# Adafruit_LSM9DS0_PCB.net
KiCad netlist of a schematic drawn in EAGLE
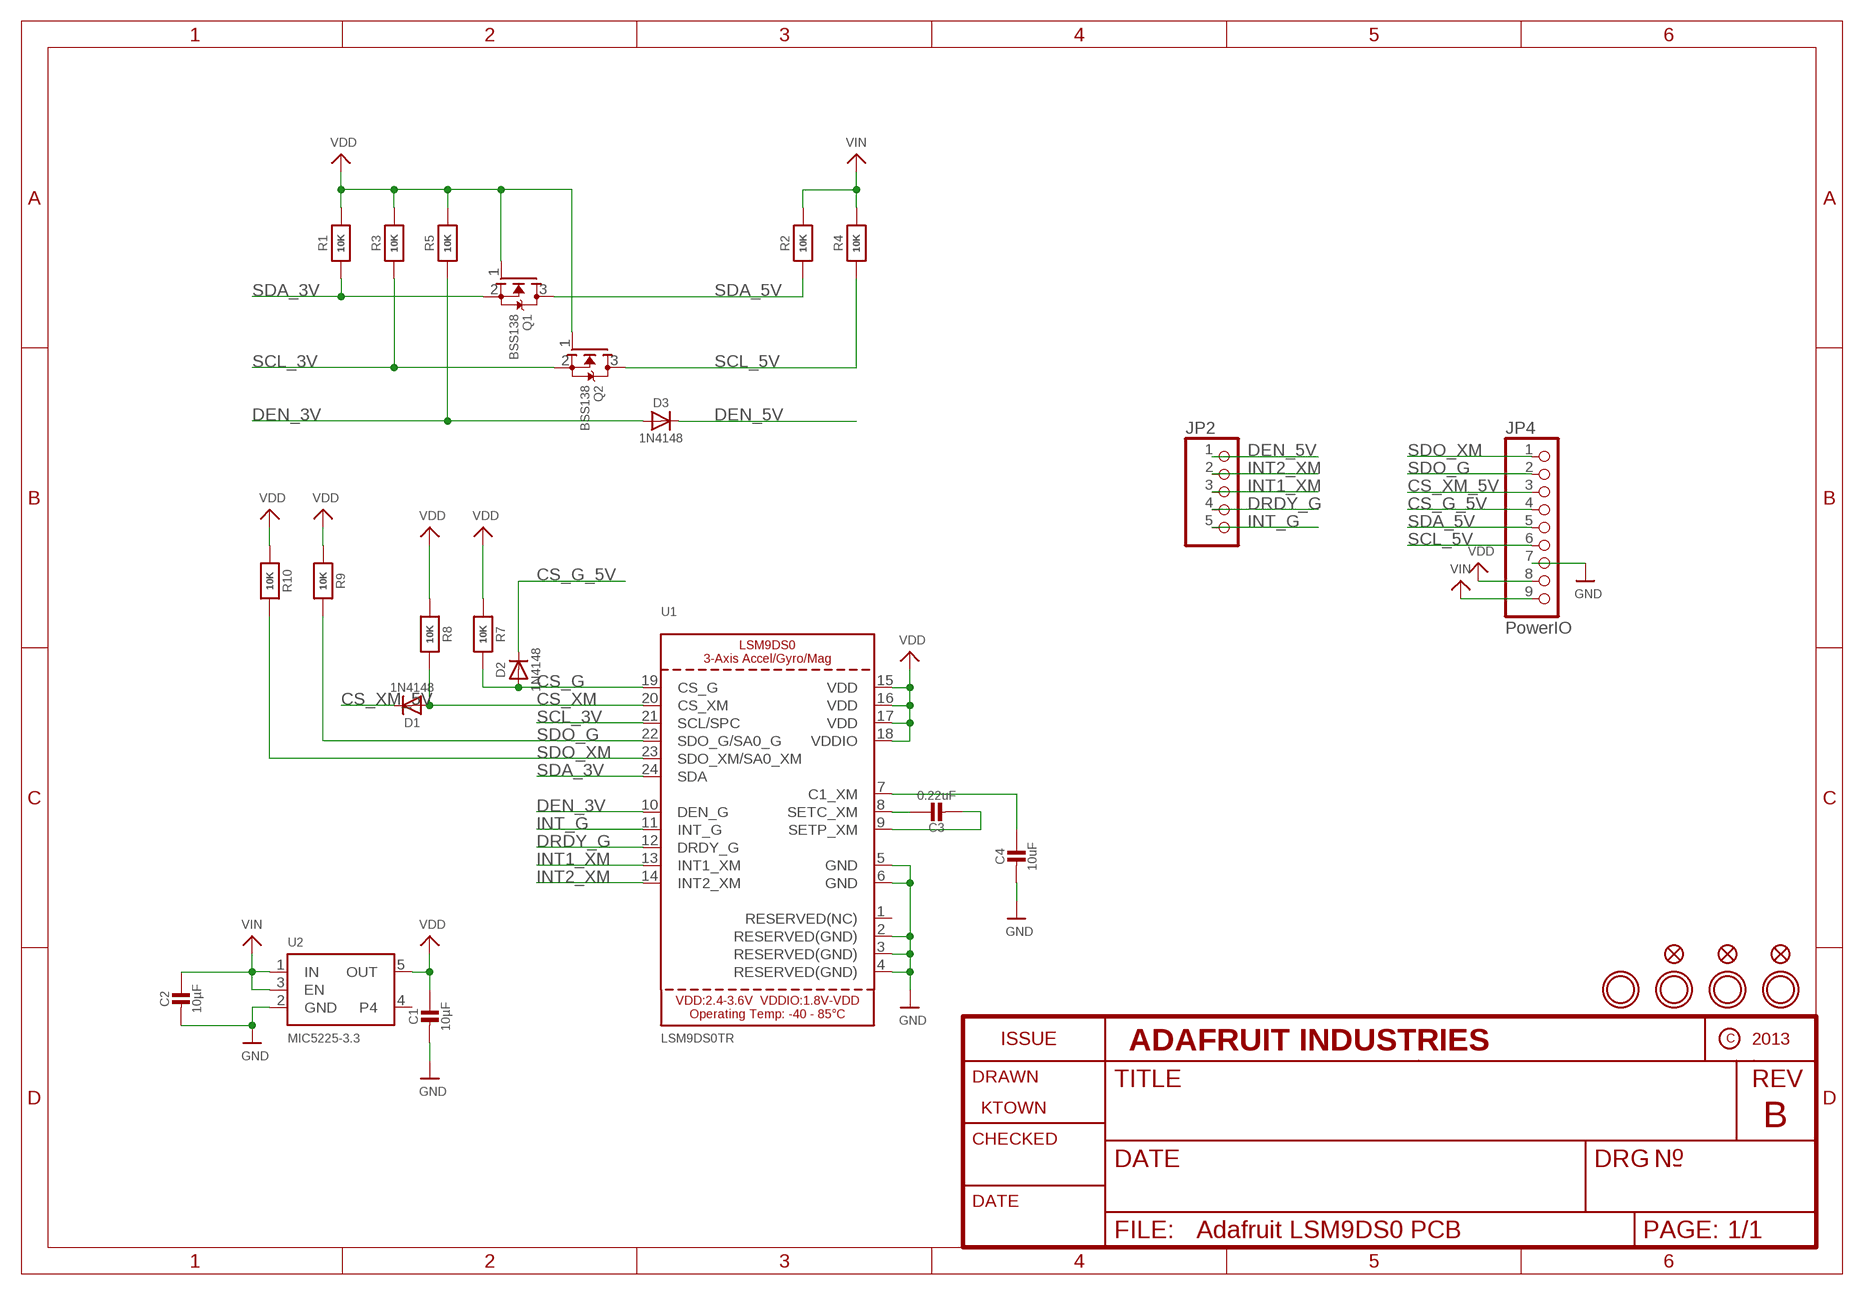
[diagram p0: schematic, sheet 1]

(export (version "E")
  (design (tool "Eeschema 10.0.6"))
  (components
    (comp (ref "C1")
      (value "10µF")
      (footprint "eagle-import:0805-NO")
      (libsource (lib "eagle-import") (part "CAP_CERAMIC0805-NOOUTLINE"))
    )
    (comp (ref "C2")
      (value "10µF")
      (footprint "eagle-import:0805-NO")
      (libsource (lib "eagle-import") (part "CAP_CERAMIC0805-NOOUTLINE"))
    )
    (comp (ref "C3")
      (value "0.22uF")
      (footprint "eagle-import:0805-NO")
      (libsource (lib "eagle-import") (part "CAP_CERAMIC0805-NOOUTLINE"))
    )
    (comp (ref "C4")
      (value "10uF")
      (footprint "eagle-import:0805-NO")
      (libsource (lib "eagle-import") (part "CAP_CERAMIC0805-NOOUTLINE"))
    )
    (comp (ref "D1")
      (value "1N4148")
      (footprint "eagle-import:SOD-323")
      (libsource (lib "eagle-import") (part "DIODESOD-323"))
    )
    (comp (ref "D2")
      (value "1N4148")
      (footprint "eagle-import:SOD-323")
      (libsource (lib "eagle-import") (part "DIODESOD-323"))
    )
    (comp (ref "D3")
      (value "1N4148")
      (footprint "eagle-import:SOD-323")
      (libsource (lib "eagle-import") (part "DIODESOD-323"))
    )
    (comp (ref "FID1")
      (value "FIDUCIAL\"\"")
      (footprint "eagle-import:FIDUCIAL_1MM")
      (libsource (lib "eagle-import") (part "FIDUCIAL{dblquote}{dblquote}"))
    )
    (comp (ref "FID2")
      (value "FIDUCIAL\"\"")
      (footprint "eagle-import:FIDUCIAL_1MM")
      (libsource (lib "eagle-import") (part "FIDUCIAL{dblquote}{dblquote}"))
    )
    (comp (ref "FID3")
      (value "FIDUCIAL\"\"")
      (footprint "eagle-import:FIDUCIAL_1MM")
      (fields (field (name "BOM") "EXCLUDE"))
      (libsource (lib "eagle-import") (part "FIDUCIAL{dblquote}{dblquote}"))
    )
    (comp (ref "JP2")
      (value "HEADER-1X570MIL")
      (footprint "eagle-import:1X05_ROUND_70")
      (libsource (lib "eagle-import") (part "HEADER-1X570MIL"))
    )
    (comp (ref "JP4")
      (value "PowerIO")
      (footprint "eagle-import:1X09_ROUND_70")
      (libsource (lib "eagle-import") (part "HEADER-1X970MIL"))
    )
    (comp (ref "Q1")
      (value "BSS138")
      (footprint "eagle-import:SOT23-WIDE")
      (libsource (lib "eagle-import") (part "MOSFET-NWIDE"))
    )
    (comp (ref "Q2")
      (value "BSS138")
      (footprint "eagle-import:SOT23-WIDE")
      (libsource (lib "eagle-import") (part "MOSFET-NWIDE"))
    )
    (comp (ref "R1")
      (value "10K")
      (footprint "eagle-import:0805-NO")
      (libsource (lib "eagle-import") (part "RESISTOR0805_NOOUTLINE"))
    )
    (comp (ref "R2")
      (value "10K")
      (footprint "eagle-import:0805-NO")
      (libsource (lib "eagle-import") (part "RESISTOR0805_NOOUTLINE"))
    )
    (comp (ref "R3")
      (value "10K")
      (footprint "eagle-import:0805-NO")
      (libsource (lib "eagle-import") (part "RESISTOR0805_NOOUTLINE"))
    )
    (comp (ref "R4")
      (value "10K")
      (footprint "eagle-import:_0805MP")
      (libsource (lib "eagle-import") (part "RESISTOR_0805MP"))
    )
    (comp (ref "R5")
      (value "10K")
      (footprint "eagle-import:0805-NO")
      (libsource (lib "eagle-import") (part "RESISTOR0805_NOOUTLINE"))
    )
    (comp (ref "R7")
      (value "10K")
      (footprint "eagle-import:0805-NO")
      (libsource (lib "eagle-import") (part "RESISTOR0805_NOOUTLINE"))
    )
    (comp (ref "R8")
      (value "10K")
      (footprint "eagle-import:0805-NO")
      (libsource (lib "eagle-import") (part "RESISTOR0805_NOOUTLINE"))
    )
    (comp (ref "R9")
      (value "10K")
      (footprint "eagle-import:0805-NO")
      (libsource (lib "eagle-import") (part "RESISTOR0805_NOOUTLINE"))
    )
    (comp (ref "R10")
      (value "10K")
      (footprint "eagle-import:0805-NO")
      (libsource (lib "eagle-import") (part "RESISTOR0805_NOOUTLINE"))
    )
    (comp (ref "U$4")
      (value "MOUNTINGHOLE2.5")
      (footprint "eagle-import:MOUNTINGHOLE_2.5_PLATED")
      (libsource (lib "eagle-import") (part "MOUNTINGHOLE2.5"))
    )
    (comp (ref "U$5")
      (value "MOUNTINGHOLE2.5")
      (footprint "eagle-import:MOUNTINGHOLE_2.5_PLATED")
      (libsource (lib "eagle-import") (part "MOUNTINGHOLE2.5"))
    )
    (comp (ref "U$6")
      (value "MOUNTINGHOLE2.5")
      (footprint "eagle-import:MOUNTINGHOLE_2.5_PLATED")
      (libsource (lib "eagle-import") (part "MOUNTINGHOLE2.5"))
    )
    (comp (ref "U$7")
      (value "MOUNTINGHOLE2.5")
      (footprint "eagle-import:MOUNTINGHOLE_2.5_PLATED")
      (libsource (lib "eagle-import") (part "MOUNTINGHOLE2.5"))
    )
    (comp (ref "U1")
      (value "LSM9DS0TR")
      (footprint "eagle-import:LGA24_4X4MM")
      (libsource (lib "eagle-import") (part "LSM9DS0"))
    )
    (comp (ref "U2")
      (value "MIC5225-3.3")
      (footprint "eagle-import:SOT23-5")
      (libsource (lib "eagle-import") (part "VREG_SOT23-5"))
    )
  )
  (nets
    (net (code "1") (name "/CS_G") (class "Default")
      (node (ref "D2") (pin "A") (pinfunction "A_A") (pintype "passive"))
      (node (ref "R7") (pin "2") (pinfunction "2_2") (pintype "passive"))
      (node (ref "U1") (pin "19") (pinfunction "CS_G_19") (pintype "bidirectional"))
    )
    (net (code "2") (name "/CS_G_5V") (class "Default")
      (node (ref "D2") (pin "C") (pinfunction "C_C") (pintype "passive"))
      (node (ref "JP4") (pin "4") (pinfunction "4_4") (pintype "passive"))
    )
    (net (code "3") (name "/CS_XM") (class "Default")
      (node (ref "D1") (pin "A") (pinfunction "A_A") (pintype "passive"))
      (node (ref "R8") (pin "2") (pinfunction "2_2") (pintype "passive"))
      (node (ref "U1") (pin "20") (pinfunction "CS_XM_20") (pintype "bidirectional"))
    )
    (net (code "4") (name "/CS_XM_5V") (class "Default")
      (node (ref "D1") (pin "C") (pinfunction "C_C") (pintype "passive"))
      (node (ref "JP4") (pin "3") (pinfunction "3_3") (pintype "passive"))
    )
    (net (code "5") (name "/DEN_3V") (class "Default")
      (node (ref "D3") (pin "A") (pinfunction "A_A") (pintype "passive"))
      (node (ref "R5") (pin "1") (pinfunction "1_1") (pintype "passive"))
      (node (ref "U1") (pin "10") (pinfunction "DEN_G_10") (pintype "bidirectional"))
    )
    (net (code "6") (name "/DEN_5V") (class "Default")
      (node (ref "D3") (pin "C") (pinfunction "C_C") (pintype "passive"))
      (node (ref "JP2") (pin "1") (pinfunction "1_1") (pintype "passive"))
    )
    (net (code "7") (name "/DRDY_G") (class "Default")
      (node (ref "JP2") (pin "4") (pinfunction "4_4") (pintype "passive"))
      (node (ref "U1") (pin "12") (pinfunction "DRDY_G_12") (pintype "bidirectional"))
    )
    (net (code "8") (name "/INT1_XM") (class "Default")
      (node (ref "JP2") (pin "3") (pinfunction "3_3") (pintype "passive"))
      (node (ref "U1") (pin "13") (pinfunction "INT1_XM_13") (pintype "bidirectional"))
    )
    (net (code "9") (name "/INT2_XM") (class "Default")
      (node (ref "JP2") (pin "2") (pinfunction "2_2") (pintype "passive"))
      (node (ref "U1") (pin "14") (pinfunction "INT2_XM_14") (pintype "bidirectional"))
    )
    (net (code "10") (name "/INT_G") (class "Default")
      (node (ref "JP2") (pin "5") (pinfunction "5_5") (pintype "passive"))
      (node (ref "U1") (pin "11") (pinfunction "INT_G_11") (pintype "bidirectional"))
    )
    (net (code "11") (name "/SCL_3V") (class "Default")
      (node (ref "Q2") (pin "2") (pinfunction "S_2") (pintype "bidirectional"))
      (node (ref "R3") (pin "1") (pinfunction "1_1") (pintype "passive"))
      (node (ref "U1") (pin "21") (pinfunction "SCL/SPC_21") (pintype "bidirectional"))
    )
    (net (code "12") (name "/SCL_5V") (class "Default")
      (node (ref "JP4") (pin "6") (pinfunction "6_6") (pintype "passive"))
      (node (ref "Q2") (pin "3") (pinfunction "D_3") (pintype "bidirectional"))
      (node (ref "R4") (pin "1") (pinfunction "1_1") (pintype "passive"))
    )
    (net (code "13") (name "/SDA_3V") (class "Default")
      (node (ref "Q1") (pin "2") (pinfunction "S_2") (pintype "bidirectional"))
      (node (ref "R1") (pin "1") (pinfunction "1_1") (pintype "passive"))
      (node (ref "U1") (pin "24") (pinfunction "SDA_24") (pintype "bidirectional"))
    )
    (net (code "14") (name "/SDA_5V") (class "Default")
      (node (ref "JP4") (pin "5") (pinfunction "5_5") (pintype "passive"))
      (node (ref "Q1") (pin "3") (pinfunction "D_3") (pintype "bidirectional"))
      (node (ref "R2") (pin "1") (pinfunction "1_1") (pintype "passive"))
    )
    (net (code "15") (name "/SDO_G") (class "Default")
      (node (ref "JP4") (pin "2") (pinfunction "2_2") (pintype "passive"))
      (node (ref "R9") (pin "2") (pinfunction "2_2") (pintype "passive"))
      (node (ref "U1") (pin "22") (pinfunction "SDO_G/SA0_G_22") (pintype "bidirectional"))
    )
    (net (code "16") (name "/SDO_XM") (class "Default")
      (node (ref "JP4") (pin "1") (pinfunction "1_1") (pintype "passive"))
      (node (ref "R10") (pin "2") (pinfunction "2_2") (pintype "passive"))
      (node (ref "U1") (pin "23") (pinfunction "SDO_XM/SA0_XM_23") (pintype "bidirectional"))
    )
    (net (code "17") (name "GND") (class "Default")
      (node (ref "C1") (pin "2") (pinfunction "2_2") (pintype "passive"))
      (node (ref "C2") (pin "2") (pinfunction "2_2") (pintype "passive"))
      (node (ref "C4") (pin "2") (pinfunction "2_2") (pintype "passive"))
      (node (ref "JP4") (pin "7") (pinfunction "7_7") (pintype "passive"))
      (node (ref "U1") (pin "2") (pinfunction "RESERVED(GND)_2") (pintype "power_in"))
      (node (ref "U1") (pin "3") (pinfunction "RESERVED(GND)_3") (pintype "power_in"))
      (node (ref "U1") (pin "4") (pinfunction "RESERVED(GND)_4") (pintype "power_in"))
      (node (ref "U1") (pin "5") (pinfunction "GND_5") (pintype "power_in"))
      (node (ref "U1") (pin "6") (pinfunction "GND_6") (pintype "power_in"))
      (node (ref "U2") (pin "2") (pinfunction "GND_2") (pintype "power_in"))
    )
    (net (code "18") (name "Net-(U1-C1_XM)") (class "Default")
      (node (ref "C4") (pin "1") (pinfunction "1_1") (pintype "passive"))
      (node (ref "U1") (pin "7") (pinfunction "C1_XM_7") (pintype "bidirectional"))
    )
    (net (code "19") (name "Net-(U1-SETC_XM)") (class "Default")
      (node (ref "C3") (pin "1") (pinfunction "1_1") (pintype "passive"))
      (node (ref "U1") (pin "8") (pinfunction "SETC_XM_8") (pintype "bidirectional"))
    )
    (net (code "20") (name "Net-(U1-SETP_XM)") (class "Default")
      (node (ref "C3") (pin "2") (pinfunction "2_2") (pintype "passive"))
      (node (ref "U1") (pin "9") (pinfunction "SETP_XM_9") (pintype "bidirectional"))
    )
    (net (code "21") (name "VDD") (class "Default")
      (node (ref "C1") (pin "1") (pinfunction "1_1") (pintype "passive"))
      (node (ref "JP4") (pin "8") (pinfunction "8_8") (pintype "passive"))
      (node (ref "Q1") (pin "1") (pinfunction "G_1") (pintype "bidirectional"))
      (node (ref "Q2") (pin "1") (pinfunction "G_1") (pintype "bidirectional"))
      (node (ref "R1") (pin "2") (pinfunction "2_2") (pintype "passive"))
      (node (ref "R10") (pin "1") (pinfunction "1_1") (pintype "passive"))
      (node (ref "R3") (pin "2") (pinfunction "2_2") (pintype "passive"))
      (node (ref "R5") (pin "2") (pinfunction "2_2") (pintype "passive"))
      (node (ref "R7") (pin "1") (pinfunction "1_1") (pintype "passive"))
      (node (ref "R8") (pin "1") (pinfunction "1_1") (pintype "passive"))
      (node (ref "R9") (pin "1") (pinfunction "1_1") (pintype "passive"))
      (node (ref "U1") (pin "15") (pinfunction "VDD_15") (pintype "power_in"))
      (node (ref "U1") (pin "16") (pinfunction "VDD_16") (pintype "power_in"))
      (node (ref "U1") (pin "17") (pinfunction "VDD_17") (pintype "power_in"))
      (node (ref "U1") (pin "18") (pinfunction "VDDIO_18") (pintype "power_in"))
      (node (ref "U2") (pin "5") (pinfunction "OUT_5") (pintype "power_in"))
    )
    (net (code "22") (name "VIN") (class "Default")
      (node (ref "C2") (pin "1") (pinfunction "1_1") (pintype "passive"))
      (node (ref "JP4") (pin "9") (pinfunction "9_9") (pintype "passive"))
      (node (ref "R2") (pin "2") (pinfunction "2_2") (pintype "passive"))
      (node (ref "R4") (pin "2") (pinfunction "2_2") (pintype "passive"))
      (node (ref "U2") (pin "1") (pinfunction "IN_1") (pintype "power_in"))
      (node (ref "U2") (pin "3") (pinfunction "EN_3") (pintype "input"))
    )
    (net (code "23") (name "unconnected-(U1-RESERVED(NC)-Pad1)") (class "Default")
      (node (ref "U1") (pin "1") (pinfunction "RESERVED(NC)_1") (pintype "no_connect"))
    )
    (net (code "24") (name "unconnected-(U2-P4-Pad4)") (class "Default")
      (node (ref "U2") (pin "4") (pinfunction "P4_4") (pintype "bidirectional"))
    )
  )
)
